# olampki.net
KiCad netlist of a schematic drawn in EAGLE
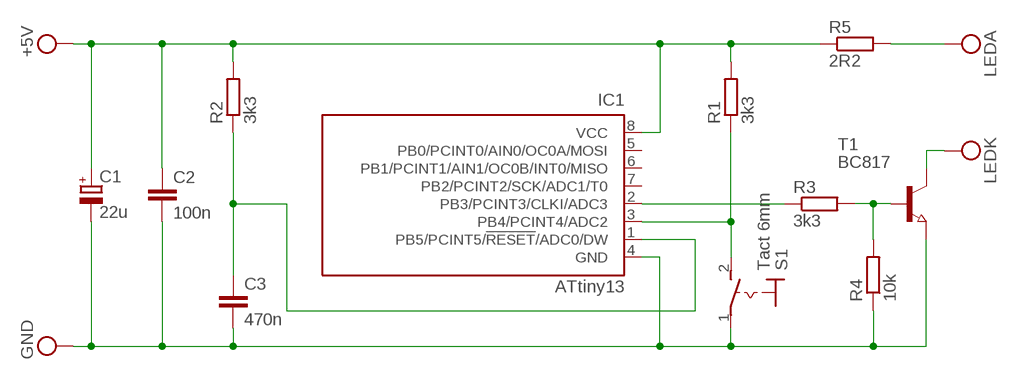
[diagram p0: schematic, sheet 1]

(export (version "E")
  (design (tool "Eeschema 10.0.6"))
  (components
    (comp (ref "C1")
      (value "22u")
      (footprint "eagle-import:085CS_1AR")
      (libsource (lib "eagle-import") (part "CPOL-EU085CS-1AR"))
    )
    (comp (ref "C2")
      (value "100n")
      (footprint "eagle-import:C2.5-3")
      (libsource (lib "eagle-import") (part "C2,5-3"))
    )
    (comp (ref "C3")
      (value "470n")
      (footprint "eagle-import:C2.5-3")
      (libsource (lib "eagle-import") (part "C2,5-3"))
    )
    (comp (ref "IC1")
      (value "ATtiny13")
      (footprint "eagle-import:8S1")
      (fields (field (name "MPN") "ATTINY13-20SSU"))
      (libsource (lib "eagle-import") (part "TINY13SSU-20"))
    )
    (comp (ref "R1")
      (value "3k3")
      (footprint "eagle-import:0204V")
      (libsource (lib "eagle-import") (part "R-EU_0204/2V"))
    )
    (comp (ref "R2")
      (value "3k3")
      (footprint "eagle-import:0204V")
      (libsource (lib "eagle-import") (part "R-EU_0204/2V"))
    )
    (comp (ref "R3")
      (value "3k3")
      (footprint "eagle-import:0204V")
      (libsource (lib "eagle-import") (part "R-EU_0204/2V"))
    )
    (comp (ref "R4")
      (value "10k")
      (footprint "eagle-import:0204V")
      (libsource (lib "eagle-import") (part "R-EU_0204/2V"))
    )
    (comp (ref "R5")
      (value "2R2")
      (footprint "eagle-import:0204V")
      (libsource (lib "eagle-import") (part "R-EU_0204/2V"))
    )
    (comp (ref "S1")
      (value "Tact 6mm")
      (footprint "eagle-import:MS243")
      (libsource (lib "eagle-import") (part "MS243"))
    )
    (comp (ref "T1")
      (value "BC817")
      (footprint "eagle-import:SOT23")
      (libsource (lib "eagle-import") (part "NPN-TRANSISTOR_SOT23"))
    )
  )
  (nets
    (net (code "1") (name "+5V") (class "Default")
      (node (ref "C1") (pin "+") (pinfunction "+_+") (pintype "passive"))
      (node (ref "C1") (pin "-") (pinfunction "-_-") (pintype "passive"))
      (node (ref "C2") (pin "1") (pinfunction "1_1") (pintype "passive"))
      (node (ref "C2") (pin "2") (pinfunction "2_2") (pintype "passive"))
      (node (ref "C3") (pin "2") (pinfunction "2_2") (pintype "passive"))
      (node (ref "IC1") (pin "4") (pinfunction "GND_4") (pintype "power_in"))
      (node (ref "IC1") (pin "8") (pinfunction "VCC_8") (pintype "power_in"))
      (node (ref "R1") (pin "2") (pinfunction "2_2") (pintype "passive"))
      (node (ref "R2") (pin "2") (pinfunction "2_2") (pintype "passive"))
      (node (ref "R4") (pin "1") (pinfunction "1_1") (pintype "passive"))
      (node (ref "R5") (pin "1") (pinfunction "1_1") (pintype "passive"))
      (node (ref "R5") (pin "2") (pinfunction "2_2") (pintype "passive"))
      (node (ref "S1") (pin "1") (pinfunction "P_1") (pintype "passive"))
      (node (ref "T1") (pin "2") (pinfunction "E_2") (pintype "passive"))
      (node (ref "T1") (pin "3") (pinfunction "C_3") (pintype "passive"))
    )
    (net (code "2") (name "Net-(IC1-PB3{slash}PCINT3{slash}CLKI{slash}ADC3)") (class "Default")
      (node (ref "IC1") (pin "2") (pinfunction "PB3/PCINT3/CLKI/ADC3_2") (pintype "bidirectional"))
      (node (ref "R3") (pin "1") (pinfunction "1_1") (pintype "passive"))
    )
    (net (code "3") (name "Net-(IC1-PB4{slash}PCINT4{slash}ADC2)") (class "Default")
      (node (ref "IC1") (pin "3") (pinfunction "PB4/PCINT4/ADC2_3") (pintype "bidirectional"))
      (node (ref "R1") (pin "1") (pinfunction "1_1") (pintype "passive"))
      (node (ref "S1") (pin "2") (pinfunction "S_2") (pintype "passive"))
    )
    (net (code "4") (name "Net-(IC1-PB5{slash}PCINT5{slash}~{RESET}{slash}ADC0{slash}DW)") (class "Default")
      (node (ref "C3") (pin "1") (pinfunction "1_1") (pintype "passive"))
      (node (ref "IC1") (pin "1") (pinfunction "PB5/PCINT5/~{RESET}/ADC0/DW_1") (pintype "bidirectional"))
      (node (ref "R2") (pin "1") (pinfunction "1_1") (pintype "passive"))
    )
    (net (code "5") (name "Net-(T1-B)") (class "Default")
      (node (ref "R3") (pin "2") (pinfunction "2_2") (pintype "passive"))
      (node (ref "R4") (pin "2") (pinfunction "2_2") (pintype "passive"))
      (node (ref "T1") (pin "1") (pinfunction "B_1") (pintype "passive"))
    )
    (net (code "6") (name "unconnected-(IC1-PB0{slash}PCINT0{slash}AIN0{slash}OC0A{slash}MOSI-Pad5)") (class "Default")
      (node (ref "IC1") (pin "5") (pinfunction "PB0/PCINT0/AIN0/OC0A/MOSI_5") (pintype "bidirectional"))
    )
    (net (code "7") (name "unconnected-(IC1-PB1{slash}PCINT1{slash}AIN1{slash}OC0B{slash}INT0{slash}MISO-Pad6)") (class "Default")
      (node (ref "IC1") (pin "6") (pinfunction "PB1/PCINT1/AIN1/OC0B/INT0/MISO_6") (pintype "bidirectional"))
    )
    (net (code "8") (name "unconnected-(IC1-PB2{slash}PCINT2{slash}SCK{slash}ADC1{slash}T0-Pad7)") (class "Default")
      (node (ref "IC1") (pin "7") (pinfunction "PB2/PCINT2/SCK/ADC1/T0_7") (pintype "bidirectional"))
    )
  )
)
